# power-bridge.net
KiCad netlist of a schematic drawn in EAGLE
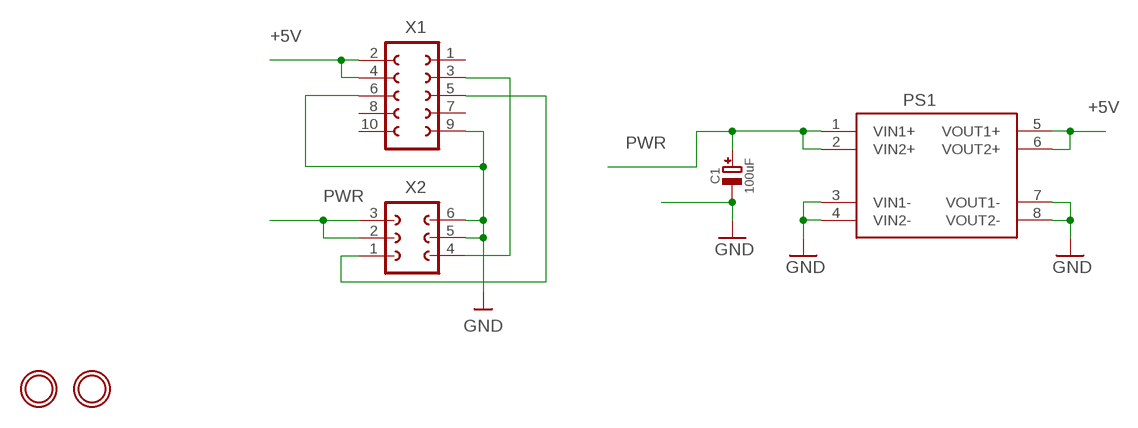
[diagram p0: schematic, sheet 1]

(export (version "E")
  (design (tool "Eeschema 10.0.6"))
  (components
    (comp (ref "C1")
      (value "100uF")
      (footprint "eagle-import:CELEC_3.5MM_8MM")
      (libsource (lib "eagle-import") (part "CAP_ELECTROLYTICPTH_3.5MMGRID_8MMDIA"))
    )
    (comp (ref "PS1")
      (value "K8801MODULE")
      (footprint "eagle-import:K8801")
      (libsource (lib "eagle-import") (part "K8801MODULE"))
    )
    (comp (ref "U$2")
      (value "MOUNTINGHOLE2.7_THICK")
      (footprint "eagle-import:MOUNTINGHOLE_2.7_PLATED_THICK")
      (libsource (lib "eagle-import") (part "MOUNTINGHOLE2.7_THICK"))
    )
    (comp (ref "U$3")
      (value "MOUNTINGHOLE2.7_THICK")
      (footprint "eagle-import:MOUNTINGHOLE_2.7_PLATED_THICK")
      (libsource (lib "eagle-import") (part "MOUNTINGHOLE2.7_THICK"))
    )
    (comp (ref "X1")
      (value "CON-FE05-2")
      (footprint "eagle-import:FE05-2")
      (libsource (lib "eagle-import") (part "CON-FE05-2"))
    )
    (comp (ref "X2")
      (value "CON-MA03-2PCB_EDGE")
      (footprint "eagle-import:PCB_EDGE_03-2")
      (libsource (lib "eagle-import") (part "CON-MA03-2PCB_EDGE"))
    )
  )
  (nets
    (net (code "1") (name "/+5V") (class "Default")
      (node (ref "PS1") (pin "5") (pinfunction "VOUT1+_5") (pintype "bidirectional"))
      (node (ref "PS1") (pin "6") (pinfunction "VOUT2+_6") (pintype "bidirectional"))
      (node (ref "X1") (pin "2") (pinfunction "2_2") (pintype "passive"))
      (node (ref "X1") (pin "4") (pinfunction "4_4") (pintype "passive"))
    )
    (net (code "2") (name "/PWR") (class "Default")
      (node (ref "C1") (pin "+") (pinfunction "+_+") (pintype "passive"))
      (node (ref "PS1") (pin "1") (pinfunction "VIN1+_1") (pintype "bidirectional"))
      (node (ref "PS1") (pin "2") (pinfunction "VIN2+_2") (pintype "bidirectional"))
      (node (ref "X2") (pin "2") (pinfunction "2_2") (pintype "passive"))
      (node (ref "X2") (pin "3") (pinfunction "3_3") (pintype "passive"))
    )
    (net (code "3") (name "GND") (class "Default")
      (node (ref "C1") (pin "-") (pinfunction "-_-") (pintype "passive"))
      (node (ref "PS1") (pin "3") (pinfunction "VIN1-_3") (pintype "bidirectional"))
      (node (ref "PS1") (pin "4") (pinfunction "VIN2-_4") (pintype "bidirectional"))
      (node (ref "PS1") (pin "7") (pinfunction "VOUT1-_7") (pintype "bidirectional"))
      (node (ref "PS1") (pin "8") (pinfunction "VOUT2-_8") (pintype "bidirectional"))
      (node (ref "X1") (pin "6") (pinfunction "6_6") (pintype "passive"))
      (node (ref "X1") (pin "9") (pinfunction "9_9") (pintype "passive"))
      (node (ref "X2") (pin "5") (pinfunction "5_5") (pintype "passive"))
      (node (ref "X2") (pin "6") (pinfunction "6_6") (pintype "passive"))
    )
    (net (code "4") (name "Net-(X1-Pad3)") (class "Default")
      (node (ref "X1") (pin "3") (pinfunction "3_3") (pintype "passive"))
      (node (ref "X2") (pin "4") (pinfunction "4_4") (pintype "passive"))
    )
    (net (code "5") (name "Net-(X1-Pad5)") (class "Default")
      (node (ref "X1") (pin "5") (pinfunction "5_5") (pintype "passive"))
      (node (ref "X2") (pin "1") (pinfunction "1_1") (pintype "passive"))
    )
    (net (code "6") (name "unconnected-(X1-Pad1)") (class "Default")
      (node (ref "X1") (pin "1") (pinfunction "1_1") (pintype "passive"))
    )
    (net (code "7") (name "unconnected-(X1-Pad7)") (class "Default")
      (node (ref "X1") (pin "7") (pinfunction "7_7") (pintype "passive"))
    )
    (net (code "8") (name "unconnected-(X1-Pad8)") (class "Default")
      (node (ref "X1") (pin "8") (pinfunction "8_8") (pintype "passive"))
    )
    (net (code "9") (name "unconnected-(X1-Pad10)") (class "Default")
      (node (ref "X1") (pin "10") (pinfunction "10_10") (pintype "passive"))
    )
  )
)
